# STLink_Schematic.net
KiCad netlist of a schematic drawn in Altium Designer
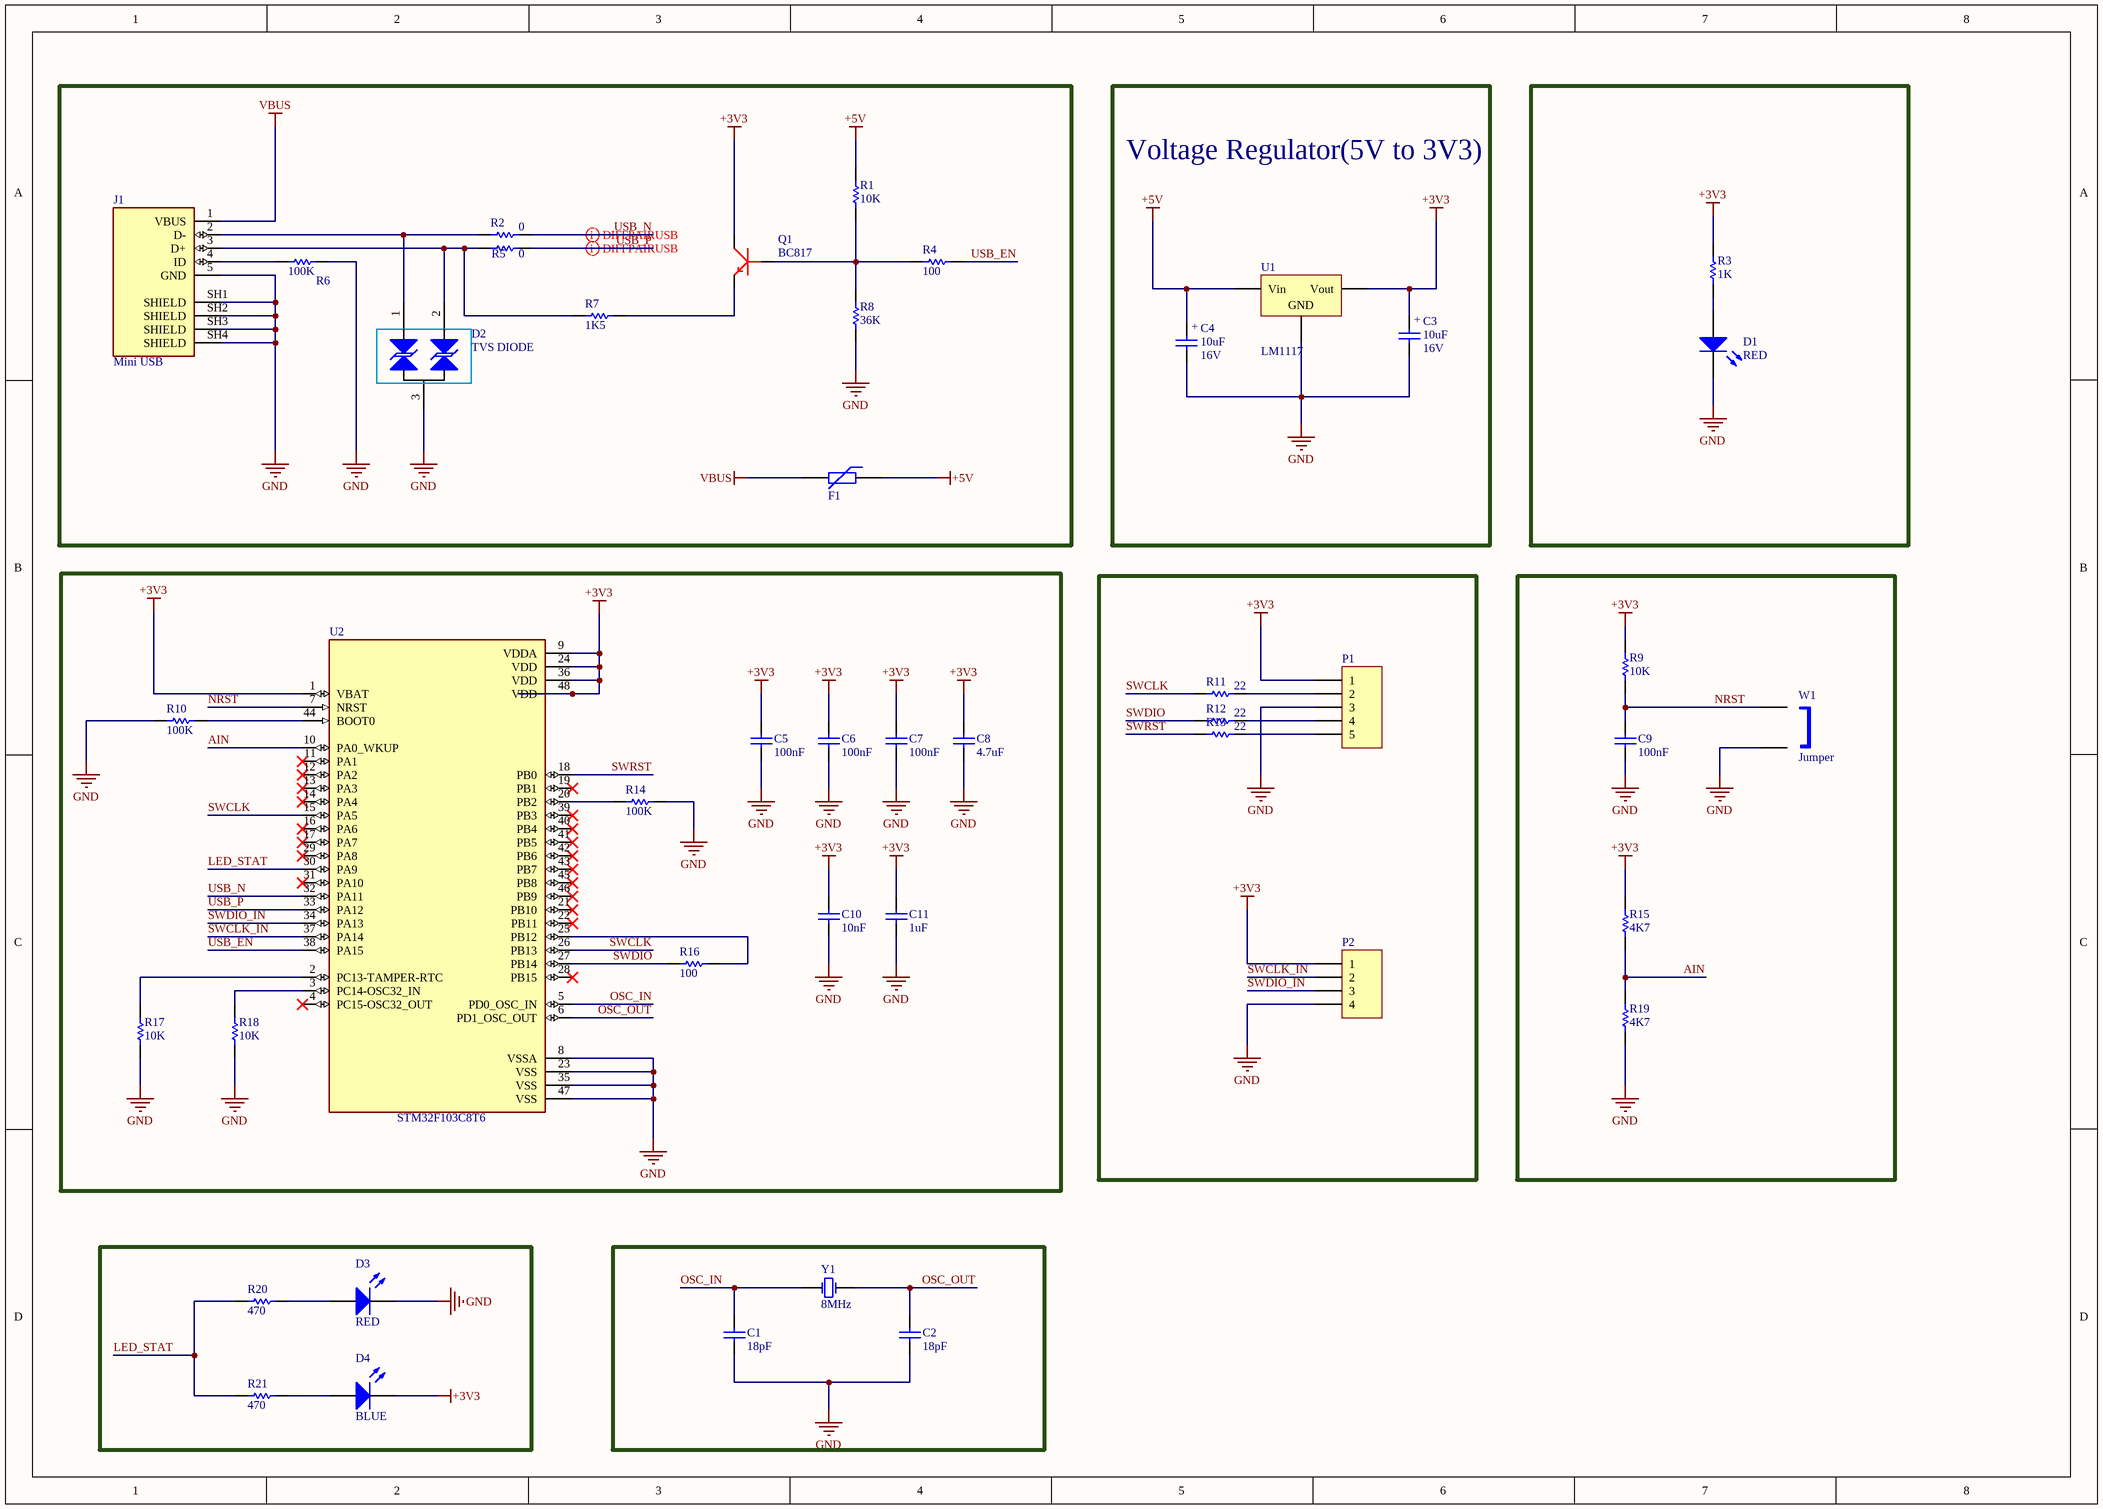
[diagram p0: STLink_Schematic.SchDoc]

(export (version "E")
  (design (tool "Eeschema 10.0.6"))
  (components
    (comp (ref "C1")
      (value "18pF")
      (footprint "C805")
      (description "Capacitor")
      (fields (field (name "DESIGNER") "Parsa Malekpour"))
      (libsource (lib "ParsaLibrary") (part "Cap"))
    )
    (comp (ref "C2")
      (value "18pF")
      (footprint "C805")
      (description "Capacitor")
      (fields (field (name "DESIGNER") "Parsa Malekpour"))
      (libsource (lib "ParsaLibrary") (part "Cap"))
    )
    (comp (ref "C3")
      (value "10uF")
      (footprint "MY_SMC_B")
      (description "Polar capacitor")
      (fields (field (name "ASID PART NUMBER") "C-AS") (field (name "VOLTE") "16V"))
      (libsource (lib "Mylib") (part "Cap Pol"))
    )
    (comp (ref "C4")
      (value "10uF")
      (footprint "MY_SMC_B")
      (description "Polar capacitor")
      (fields (field (name "ASID PART NUMBER") "C-AS") (field (name "VOLTE") "16V"))
      (libsource (lib "Mylib") (part "Cap Pol"))
    )
    (comp (ref "C5")
      (value "100nF")
      (footprint "C805")
      (description "Capacitor")
      (fields (field (name "DESIGNER") "Parsa Malekpour"))
      (libsource (lib "ParsaLibrary") (part "Cap"))
    )
    (comp (ref "C6")
      (value "100nF")
      (footprint "C805")
      (description "Capacitor")
      (fields (field (name "DESIGNER") "Parsa Malekpour"))
      (libsource (lib "ParsaLibrary") (part "Cap"))
    )
    (comp (ref "C7")
      (value "100nF")
      (footprint "C805")
      (description "Capacitor")
      (fields (field (name "DESIGNER") "Parsa Malekpour"))
      (libsource (lib "ParsaLibrary") (part "Cap"))
    )
    (comp (ref "C8")
      (value "4.7uF")
      (footprint "C805")
      (description "Capacitor")
      (fields (field (name "DESIGNER") "Parsa Malekpour"))
      (libsource (lib "ParsaLibrary") (part "Cap"))
    )
    (comp (ref "C9")
      (value "100nF")
      (footprint "C805")
      (description "Capacitor")
      (fields (field (name "DESIGNER") "Parsa Malekpour"))
      (libsource (lib "ParsaLibrary") (part "Cap"))
    )
    (comp (ref "C10")
      (value "10nF")
      (footprint "C805")
      (description "Capacitor")
      (fields (field (name "DESIGNER") "Parsa Malekpour"))
      (libsource (lib "ParsaLibrary") (part "Cap"))
    )
    (comp (ref "C11")
      (value "1uF")
      (footprint "C805")
      (description "Capacitor")
      (fields (field (name "DESIGNER") "Parsa Malekpour"))
      (libsource (lib "ParsaLibrary") (part "Cap"))
    )
    (comp (ref "D1")
      (value "RED")
      (footprint "MY_LED_1206")
      (description "Typical INFRARED GaAs LED")
      (fields (field (name "ASID PART NUMBER") "LED-AS"))
      (libsource (lib "Mylib") (part "LED"))
    )
    (comp (ref "D2") (value "TVS DIODE") (footprint "SOT-23") (libsource (lib "ParsaLibrary") (part "SM712")))
    (comp (ref "D3")
      (value "RED")
      (footprint "MY_LED_0805")
      (description "Typical INFRARED GaAs LED")
      (fields (field (name "ASID PART NUMBER") "LED-AS"))
      (libsource (lib "Mylib") (part "LED"))
    )
    (comp (ref "D4")
      (value "BLUE")
      (footprint "MY_LED_0805")
      (description "Typical INFRARED GaAs LED")
      (fields (field (name "ASID PART NUMBER") "LED-AS"))
      (libsource (lib "Mylib") (part "LED"))
    )
    (comp (ref "F1")
      (value "~")
      (footprint "PTC-0805")
      (description "PTC")
      (libsource (lib "ParsaLibrary") (part "PTC"))
    )
    (comp (ref "J1")
      (value "Mini USB")
      (footprint "MiniUSB")
      (description "MINI USB 2.0- B Type Receptacle conn. Right Angle Surface Mount Type")
      (fields (field (name "MF") "Amphenol ICC") (field (name "MP") "10033526-N3212LF"))
      (libsource (lib "STLink_V2_Design") (part "Mini USB"))
    )
    (comp (ref "P1")
      (value "Header 5")
      (footprint "My_1X05")
      (description "Header, 5-Pin")
      (fields (field (name "ASID PART NUMBER") "Header 5-AS"))
      (libsource (lib "Mylib") (part "Header 5"))
    )
    (comp (ref "P2")
      (value "Header 4")
      (footprint "My_1X04")
      (description "Header, 4-Pin")
      (fields (field (name "ASID PART NUMBER") "Header 4-AS"))
      (libsource (lib "Mylib") (part "Header 4"))
    )
    (comp (ref "Q1")
      (value "BC817")
      (footprint "SOT23_3")
      (libsource (lib "Led_Switching") (part "bc817-16"))
    )
    (comp (ref "R1")
      (value "10K")
      (footprint "R805")
      (description "Resistor")
      (fields (field (name "DESIGNER") "Parsa Malekpour"))
      (libsource (lib "ParsaLibrary") (part "Resistor"))
    )
    (comp (ref "R2")
      (value "0")
      (footprint "R805")
      (description "Resistor")
      (fields (field (name "DESIGNER") "Parsa Malekpour"))
      (libsource (lib "ParsaLibrary") (part "Resistor"))
    )
    (comp (ref "R3")
      (value "1K")
      (footprint "R805")
      (description "Resistor")
      (fields (field (name "DESIGNER") "Parsa Malekpour"))
      (libsource (lib "ParsaLibrary") (part "Resistor"))
    )
    (comp (ref "R4")
      (value "100")
      (footprint "R805")
      (description "Resistor")
      (fields (field (name "DESIGNER") "Parsa Malekpour"))
      (libsource (lib "ParsaLibrary") (part "Resistor"))
    )
    (comp (ref "R5")
      (value "0")
      (footprint "R805")
      (description "Resistor")
      (fields (field (name "DESIGNER") "Parsa Malekpour"))
      (libsource (lib "ParsaLibrary") (part "Resistor"))
    )
    (comp (ref "R6")
      (value "100K")
      (footprint "R805")
      (description "Resistor")
      (fields (field (name "DESIGNER") "Parsa Malekpour"))
      (libsource (lib "ParsaLibrary") (part "Resistor"))
    )
    (comp (ref "R7")
      (value "1K5")
      (footprint "R805")
      (description "Resistor")
      (fields (field (name "DESIGNER") "Parsa Malekpour"))
      (libsource (lib "ParsaLibrary") (part "Resistor"))
    )
    (comp (ref "R8")
      (value "36K")
      (footprint "R805")
      (description "Resistor")
      (fields (field (name "DESIGNER") "Parsa Malekpour"))
      (libsource (lib "ParsaLibrary") (part "Resistor"))
    )
    (comp (ref "R9")
      (value "10K")
      (footprint "R805")
      (description "Resistor")
      (fields (field (name "DESIGNER") "Parsa Malekpour"))
      (libsource (lib "ParsaLibrary") (part "Resistor"))
    )
    (comp (ref "R10")
      (value "100K")
      (footprint "R805")
      (description "Resistor")
      (fields (field (name "DESIGNER") "Parsa Malekpour"))
      (libsource (lib "ParsaLibrary") (part "Resistor"))
    )
    (comp (ref "R11")
      (value "22")
      (footprint "R805")
      (description "Resistor")
      (fields (field (name "DESIGNER") "Parsa Malekpour"))
      (libsource (lib "ParsaLibrary") (part "Resistor"))
    )
    (comp (ref "R12")
      (value "22")
      (footprint "R805")
      (description "Resistor")
      (fields (field (name "DESIGNER") "Parsa Malekpour"))
      (libsource (lib "ParsaLibrary") (part "Resistor"))
    )
    (comp (ref "R13")
      (value "22")
      (footprint "R805")
      (description "Resistor")
      (fields (field (name "DESIGNER") "Parsa Malekpour"))
      (libsource (lib "ParsaLibrary") (part "Resistor"))
    )
    (comp (ref "R14")
      (value "100K")
      (footprint "R805")
      (description "Resistor")
      (fields (field (name "DESIGNER") "Parsa Malekpour"))
      (libsource (lib "ParsaLibrary") (part "Resistor"))
    )
    (comp (ref "R15")
      (value "4K7")
      (footprint "R805")
      (description "Resistor")
      (fields (field (name "DESIGNER") "Parsa Malekpour"))
      (libsource (lib "ParsaLibrary") (part "Resistor"))
    )
    (comp (ref "R16")
      (value "100")
      (footprint "R805")
      (description "Resistor")
      (fields (field (name "DESIGNER") "Parsa Malekpour"))
      (libsource (lib "ParsaLibrary") (part "Resistor"))
    )
    (comp (ref "R17")
      (value "10K")
      (footprint "R805")
      (description "Resistor")
      (fields (field (name "DESIGNER") "Parsa Malekpour"))
      (libsource (lib "ParsaLibrary") (part "Resistor"))
    )
    (comp (ref "R18")
      (value "10K")
      (footprint "R805")
      (description "Resistor")
      (fields (field (name "DESIGNER") "Parsa Malekpour"))
      (libsource (lib "ParsaLibrary") (part "Resistor"))
    )
    (comp (ref "R19")
      (value "4K7")
      (footprint "R805")
      (description "Resistor")
      (fields (field (name "DESIGNER") "Parsa Malekpour"))
      (libsource (lib "ParsaLibrary") (part "Resistor"))
    )
    (comp (ref "R20")
      (value "470")
      (footprint "R805")
      (description "Resistor")
      (fields (field (name "DESIGNER") "Parsa Malekpour"))
      (libsource (lib "ParsaLibrary") (part "Resistor"))
    )
    (comp (ref "R21")
      (value "470")
      (footprint "R805")
      (description "Resistor")
      (fields (field (name "DESIGNER") "Parsa Malekpour"))
      (libsource (lib "ParsaLibrary") (part "Resistor"))
    )
    (comp (ref "U1")
      (value "LM1117")
      (footprint "MY_SOT223")
      (description "Low Drop Voltage Reg")
      (fields (field (name "ASID PART NUMBER") "LM1117-AS"))
      (libsource (lib "Mylib") (part "LM1117"))
    )
    (comp (ref "U2")
      (value "STM32F103C8T6")
      (footprint "QFP50P900X900X160-48N")
      (description "ARM® Cortex®-M3 STM32F1 Microcontroller IC 32-Bit 72MHz 64KB (64K x 8) FLASH 48-LQFP (7x7)")
      (fields (field (name "MF") "STMicroelectronics"))
      (libsource (lib "STLink_V2_Design") (part "STM32F103C8T6"))
    )
    (comp (ref "W1")
      (value "Jumper")
      (footprint "My_1X02")
      (description "Jumper Wire")
      (fields (field (name "ASID PART NUMBER") "Jumper-AS"))
      (libsource (lib "Mylib") (part "Jumper"))
    )
    (comp (ref "Y1")
      (value "8MHz")
      (footprint "XTAL-SMD")
      (description "Crystal Oscillator")
      (fields (field (name "DESIGNER") "Parsa Malekpour") (field (name "EMAIL") "Malekpour.parsa@Gmail.com"))
      (libsource (lib "ParsaLibrary") (part "XTAL"))
    )
  )
  (nets
    (net (code "1") (name "+3V3") (class "Default")
      (node (ref "C10") (pin "2") (pinfunction "2_2") (pintype "passive"))
      (node (ref "C11") (pin "2") (pinfunction "2_2") (pintype "passive"))
      (node (ref "C3") (pin "+") (pinfunction "+_+") (pintype "passive"))
      (node (ref "C5") (pin "2") (pinfunction "2_2") (pintype "passive"))
      (node (ref "C6") (pin "2") (pinfunction "2_2") (pintype "passive"))
      (node (ref "C7") (pin "2") (pinfunction "2_2") (pintype "passive"))
      (node (ref "C8") (pin "2") (pinfunction "2_2") (pintype "passive"))
      (node (ref "D4") (pin "K") (pinfunction "K_K") (pintype "passive"))
      (node (ref "P1") (pin "1") (pinfunction "1_1") (pintype "passive"))
      (node (ref "P2") (pin "1") (pinfunction "1_1") (pintype "passive"))
      (node (ref "Q1") (pin "3") (pinfunction "C_3") (pintype "passive"))
      (node (ref "R15") (pin "1") (pinfunction "1_1") (pintype "passive"))
      (node (ref "R3") (pin "2") (pinfunction "2_2") (pintype "passive"))
      (node (ref "R9") (pin "1") (pinfunction "1_1") (pintype "passive"))
      (node (ref "U1") (pin "2") (pinfunction "Vout_2") (pintype "passive"))
      (node (ref "U2") (pin "1") (pinfunction "VBAT_1") (pintype "bidirectional"))
      (node (ref "U2") (pin "24") (pinfunction "VDD_24") (pintype "power_in"))
      (node (ref "U2") (pin "36") (pinfunction "VDD_36") (pintype "power_in"))
      (node (ref "U2") (pin "48") (pinfunction "VDD_48") (pintype "power_in"))
      (node (ref "U2") (pin "9") (pinfunction "VDDA_9") (pintype "power_in"))
    )
    (net (code "2") (name "+5V") (class "Default")
      (node (ref "C4") (pin "+") (pinfunction "+_+") (pintype "passive"))
      (node (ref "F1") (pin "1") (pinfunction "1_1") (pintype "passive"))
      (node (ref "R1") (pin "2") (pinfunction "2_2") (pintype "passive"))
      (node (ref "U1") (pin "3") (pinfunction "Vin_3") (pintype "passive"))
    )
    (net (code "3") (name "/AIN") (class "Default")
      (node (ref "R15") (pin "2") (pinfunction "2_2") (pintype "passive"))
      (node (ref "R19") (pin "1") (pinfunction "1_1") (pintype "passive"))
      (node (ref "U2") (pin "10") (pinfunction "PA0_WKUP_10") (pintype "bidirectional"))
    )
    (net (code "4") (name "/LED_STAT") (class "Default")
      (node (ref "R20") (pin "2") (pinfunction "2_2") (pintype "passive"))
      (node (ref "R21") (pin "2") (pinfunction "2_2") (pintype "passive"))
      (node (ref "U2") (pin "30") (pinfunction "PA9_30") (pintype "bidirectional"))
    )
    (net (code "5") (name "/NRST") (class "Default")
      (node (ref "C9") (pin "2") (pinfunction "2_2") (pintype "passive"))
      (node (ref "R9") (pin "2") (pinfunction "2_2") (pintype "passive"))
      (node (ref "U2") (pin "7") (pinfunction "NRST_7") (pintype "input"))
      (node (ref "W1") (pin "1") (pinfunction "1_1") (pintype "passive"))
    )
    (net (code "6") (name "/OSC_IN") (class "Default")
      (node (ref "C1") (pin "2") (pinfunction "2_2") (pintype "passive"))
      (node (ref "U2") (pin "5") (pinfunction "PD0_OSC_IN_5") (pintype "bidirectional"))
      (node (ref "Y1") (pin "1") (pinfunction "OSC1_1") (pintype "passive"))
    )
    (net (code "7") (name "/OSC_OUT") (class "Default")
      (node (ref "C2") (pin "2") (pinfunction "2_2") (pintype "passive"))
      (node (ref "U2") (pin "6") (pinfunction "PD1_OSC_OUT_6") (pintype "bidirectional"))
      (node (ref "Y1") (pin "2") (pinfunction "OSC2_2") (pintype "passive"))
    )
    (net (code "8") (name "/SWCLK") (class "Default")
      (node (ref "R11") (pin "2") (pinfunction "2_2") (pintype "passive"))
      (node (ref "U2") (pin "15") (pinfunction "PA5_15") (pintype "bidirectional"))
      (node (ref "U2") (pin "26") (pinfunction "PB13_26") (pintype "bidirectional"))
    )
    (net (code "9") (name "/SWCLK_IN") (class "Default")
      (node (ref "P2") (pin "2") (pinfunction "2_2") (pintype "passive"))
      (node (ref "U2") (pin "37") (pinfunction "PA14_37") (pintype "bidirectional"))
    )
    (net (code "10") (name "/SWDIO") (class "Default")
      (node (ref "R12") (pin "2") (pinfunction "2_2") (pintype "passive"))
      (node (ref "R16") (pin "2") (pinfunction "2_2") (pintype "passive"))
      (node (ref "U2") (pin "27") (pinfunction "PB14_27") (pintype "bidirectional"))
    )
    (net (code "11") (name "/SWDIO_IN") (class "Default")
      (node (ref "P2") (pin "3") (pinfunction "3_3") (pintype "passive"))
      (node (ref "U2") (pin "34") (pinfunction "PA13_34") (pintype "bidirectional"))
    )
    (net (code "12") (name "/SWRST") (class "Default")
      (node (ref "R13") (pin "2") (pinfunction "2_2") (pintype "passive"))
      (node (ref "U2") (pin "18") (pinfunction "PB0_18") (pintype "bidirectional"))
    )
    (net (code "13") (name "/USB_EN") (class "Default")
      (node (ref "R4") (pin "1") (pinfunction "1_1") (pintype "passive"))
      (node (ref "U2") (pin "38") (pinfunction "PA15_38") (pintype "bidirectional"))
    )
    (net (code "14") (name "/USB_N") (class "Default")
      (node (ref "R2") (pin "2") (pinfunction "2_2") (pintype "passive"))
      (node (ref "U2") (pin "32") (pinfunction "PA11_32") (pintype "bidirectional"))
    )
    (net (code "15") (name "/USB_P") (class "Default")
      (node (ref "R5") (pin "2") (pinfunction "2_2") (pintype "passive"))
      (node (ref "U2") (pin "33") (pinfunction "PA12_33") (pintype "bidirectional"))
    )
    (net (code "16") (name "GND") (class "Default")
      (node (ref "C1") (pin "1") (pinfunction "1_1") (pintype "passive"))
      (node (ref "C10") (pin "1") (pinfunction "1_1") (pintype "passive"))
      (node (ref "C11") (pin "1") (pinfunction "1_1") (pintype "passive"))
      (node (ref "C2") (pin "1") (pinfunction "1_1") (pintype "passive"))
      (node (ref "C3") (pin "-") (pinfunction "-_-") (pintype "passive"))
      (node (ref "C4") (pin "-") (pinfunction "-_-") (pintype "passive"))
      (node (ref "C5") (pin "1") (pinfunction "1_1") (pintype "passive"))
      (node (ref "C6") (pin "1") (pinfunction "1_1") (pintype "passive"))
      (node (ref "C7") (pin "1") (pinfunction "1_1") (pintype "passive"))
      (node (ref "C8") (pin "1") (pinfunction "1_1") (pintype "passive"))
      (node (ref "C9") (pin "1") (pinfunction "1_1") (pintype "passive"))
      (node (ref "D1") (pin "K") (pinfunction "K_K") (pintype "passive"))
      (node (ref "D2") (pin "3") (pinfunction "A_3") (pintype "passive"))
      (node (ref "D3") (pin "K") (pinfunction "K_K") (pintype "passive"))
      (node (ref "J1") (pin "5") (pinfunction "GND_5") (pintype "power_in"))
      (node (ref "J1") (pin "SH1") (pinfunction "SHIELD_SH1") (pintype "passive"))
      (node (ref "J1") (pin "SH2") (pinfunction "SHIELD_SH2") (pintype "passive"))
      (node (ref "J1") (pin "SH3") (pinfunction "SHIELD_SH3") (pintype "passive"))
      (node (ref "J1") (pin "SH4") (pinfunction "SHIELD_SH4") (pintype "passive"))
      (node (ref "P1") (pin "3") (pinfunction "3_3") (pintype "passive"))
      (node (ref "P2") (pin "4") (pinfunction "4_4") (pintype "passive"))
      (node (ref "R10") (pin "2") (pinfunction "2_2") (pintype "passive"))
      (node (ref "R14") (pin "1") (pinfunction "1_1") (pintype "passive"))
      (node (ref "R17") (pin "2") (pinfunction "2_2") (pintype "passive"))
      (node (ref "R18") (pin "2") (pinfunction "2_2") (pintype "passive"))
      (node (ref "R19") (pin "2") (pinfunction "2_2") (pintype "passive"))
      (node (ref "R6") (pin "2") (pinfunction "2_2") (pintype "passive"))
      (node (ref "R8") (pin "1") (pinfunction "1_1") (pintype "passive"))
      (node (ref "U1") (pin "1") (pinfunction "GND_1") (pintype "passive"))
      (node (ref "U2") (pin "23") (pinfunction "VSS_23") (pintype "power_in"))
      (node (ref "U2") (pin "35") (pinfunction "VSS_35") (pintype "power_in"))
      (node (ref "U2") (pin "47") (pinfunction "VSS_47") (pintype "power_in"))
      (node (ref "U2") (pin "8") (pinfunction "VSSA_8") (pintype "power_in"))
      (node (ref "W1") (pin "2") (pinfunction "2_2") (pintype "passive"))
    )
    (net (code "17") (name "Net-(D1-PadA)") (class "Default")
      (node (ref "D1") (pin "A") (pinfunction "A_A") (pintype "passive"))
      (node (ref "R3") (pin "1") (pinfunction "1_1") (pintype "passive"))
    )
    (net (code "18") (name "Net-(D3-PadA)") (class "Default")
      (node (ref "D3") (pin "A") (pinfunction "A_A") (pintype "passive"))
      (node (ref "R20") (pin "1") (pinfunction "1_1") (pintype "passive"))
    )
    (net (code "19") (name "Net-(D4-PadA)") (class "Default")
      (node (ref "D4") (pin "A") (pinfunction "A_A") (pintype "passive"))
      (node (ref "R21") (pin "1") (pinfunction "1_1") (pintype "passive"))
    )
    (net (code "20") (name "Net-(J1-D+)") (class "Default")
      (node (ref "D2") (pin "2") (pinfunction "K_2") (pintype "passive"))
      (node (ref "J1") (pin "3") (pinfunction "D+_3") (pintype "bidirectional"))
      (node (ref "R5") (pin "1") (pinfunction "1_1") (pintype "passive"))
      (node (ref "R7") (pin "1") (pinfunction "1_1") (pintype "passive"))
    )
    (net (code "21") (name "Net-(J1-D-)") (class "Default")
      (node (ref "D2") (pin "1") (pinfunction "K_1") (pintype "passive"))
      (node (ref "J1") (pin "2") (pinfunction "D-_2") (pintype "bidirectional"))
      (node (ref "R2") (pin "1") (pinfunction "1_1") (pintype "passive"))
    )
    (net (code "22") (name "Net-(J1-ID)") (class "Default")
      (node (ref "J1") (pin "4") (pinfunction "ID_4") (pintype "bidirectional"))
      (node (ref "R6") (pin "1") (pinfunction "1_1") (pintype "passive"))
    )
    (net (code "23") (name "Net-(P1-Pad2)") (class "Default")
      (node (ref "P1") (pin "2") (pinfunction "2_2") (pintype "passive"))
      (node (ref "R11") (pin "1") (pinfunction "1_1") (pintype "passive"))
    )
    (net (code "24") (name "Net-(P1-Pad4)") (class "Default")
      (node (ref "P1") (pin "4") (pinfunction "4_4") (pintype "passive"))
      (node (ref "R12") (pin "1") (pinfunction "1_1") (pintype "passive"))
    )
    (net (code "25") (name "Net-(P1-Pad5)") (class "Default")
      (node (ref "P1") (pin "5") (pinfunction "5_5") (pintype "passive"))
      (node (ref "R13") (pin "1") (pinfunction "1_1") (pintype "passive"))
    )
    (net (code "26") (name "Net-(Q1-B)") (class "Default")
      (node (ref "Q1") (pin "1") (pinfunction "B_1") (pintype "passive"))
      (node (ref "R1") (pin "1") (pinfunction "1_1") (pintype "passive"))
      (node (ref "R4") (pin "2") (pinfunction "2_2") (pintype "passive"))
      (node (ref "R8") (pin "2") (pinfunction "2_2") (pintype "passive"))
    )
    (net (code "27") (name "Net-(Q1-E)") (class "Default")
      (node (ref "Q1") (pin "2") (pinfunction "E_2") (pintype "passive"))
      (node (ref "R7") (pin "2") (pinfunction "2_2") (pintype "passive"))
    )
    (net (code "28") (name "Net-(U2-BOOT0)") (class "Default")
      (node (ref "R10") (pin "1") (pinfunction "1_1") (pintype "passive"))
      (node (ref "U2") (pin "44") (pinfunction "BOOT0_44") (pintype "input"))
    )
    (net (code "29") (name "Net-(U2-PB2)") (class "Default")
      (node (ref "R14") (pin "2") (pinfunction "2_2") (pintype "passive"))
      (node (ref "U2") (pin "20") (pinfunction "PB2_20") (pintype "bidirectional"))
    )
    (net (code "30") (name "Net-(U2-PB12)") (class "Default")
      (node (ref "R16") (pin "1") (pinfunction "1_1") (pintype "passive"))
      (node (ref "U2") (pin "25") (pinfunction "PB12_25") (pintype "bidirectional"))
    )
    (net (code "31") (name "Net-(U2-PC13-TAMPER-RTC)") (class "Default")
      (node (ref "R17") (pin "1") (pinfunction "1_1") (pintype "passive"))
      (node (ref "U2") (pin "2") (pinfunction "PC13-TAMPER-RTC_2") (pintype "bidirectional"))
    )
    (net (code "32") (name "Net-(U2-PC14-OSC32_IN)") (class "Default")
      (node (ref "R18") (pin "1") (pinfunction "1_1") (pintype "passive"))
      (node (ref "U2") (pin "3") (pinfunction "PC14-OSC32_IN_3") (pintype "bidirectional"))
    )
    (net (code "33") (name "VBUS") (class "Default")
      (node (ref "F1") (pin "2") (pinfunction "2_2") (pintype "passive"))
      (node (ref "J1") (pin "1") (pinfunction "VBUS_1") (pintype "power_in"))
    )
    (net (code "34") (name "unconnected-(U2-PA1-Pad11)") (class "Default")
      (node (ref "U2") (pin "11") (pinfunction "PA1_11") (pintype "bidirectional+no_connect"))
    )
    (net (code "35") (name "unconnected-(U2-PA2-Pad12)") (class "Default")
      (node (ref "U2") (pin "12") (pinfunction "PA2_12") (pintype "bidirectional+no_connect"))
    )
    (net (code "36") (name "unconnected-(U2-PA3-Pad13)") (class "Default")
      (node (ref "U2") (pin "13") (pinfunction "PA3_13") (pintype "bidirectional+no_connect"))
    )
    (net (code "37") (name "unconnected-(U2-PA4-Pad14)") (class "Default")
      (node (ref "U2") (pin "14") (pinfunction "PA4_14") (pintype "bidirectional+no_connect"))
    )
    (net (code "38") (name "unconnected-(U2-PA6-Pad16)") (class "Default")
      (node (ref "U2") (pin "16") (pinfunction "PA6_16") (pintype "bidirectional+no_connect"))
    )
    (net (code "39") (name "unconnected-(U2-PA7-Pad17)") (class "Default")
      (node (ref "U2") (pin "17") (pinfunction "PA7_17") (pintype "bidirectional+no_connect"))
    )
    (net (code "40") (name "unconnected-(U2-PA8-Pad29)") (class "Default")
      (node (ref "U2") (pin "29") (pinfunction "PA8_29") (pintype "bidirectional+no_connect"))
    )
    (net (code "41") (name "unconnected-(U2-PA10-Pad31)") (class "Default")
      (node (ref "U2") (pin "31") (pinfunction "PA10_31") (pintype "bidirectional+no_connect"))
    )
    (net (code "42") (name "unconnected-(U2-PB1-Pad19)") (class "Default")
      (node (ref "U2") (pin "19") (pinfunction "PB1_19") (pintype "bidirectional+no_connect"))
    )
    (net (code "43") (name "unconnected-(U2-PB3-Pad39)") (class "Default")
      (node (ref "U2") (pin "39") (pinfunction "PB3_39") (pintype "bidirectional+no_connect"))
    )
    (net (code "44") (name "unconnected-(U2-PB4-Pad40)") (class "Default")
      (node (ref "U2") (pin "40") (pinfunction "PB4_40") (pintype "bidirectional+no_connect"))
    )
    (net (code "45") (name "unconnected-(U2-PB5-Pad41)") (class "Default")
      (node (ref "U2") (pin "41") (pinfunction "PB5_41") (pintype "bidirectional+no_connect"))
    )
    (net (code "46") (name "unconnected-(U2-PB6-Pad42)") (class "Default")
      (node (ref "U2") (pin "42") (pinfunction "PB6_42") (pintype "bidirectional+no_connect"))
    )
    (net (code "47") (name "unconnected-(U2-PB7-Pad43)") (class "Default")
      (node (ref "U2") (pin "43") (pinfunction "PB7_43") (pintype "bidirectional+no_connect"))
    )
    (net (code "48") (name "unconnected-(U2-PB8-Pad45)") (class "Default")
      (node (ref "U2") (pin "45") (pinfunction "PB8_45") (pintype "bidirectional+no_connect"))
    )
    (net (code "49") (name "unconnected-(U2-PB9-Pad46)") (class "Default")
      (node (ref "U2") (pin "46") (pinfunction "PB9_46") (pintype "bidirectional+no_connect"))
    )
    (net (code "50") (name "unconnected-(U2-PB10-Pad21)") (class "Default")
      (node (ref "U2") (pin "21") (pinfunction "PB10_21") (pintype "bidirectional+no_connect"))
    )
    (net (code "51") (name "unconnected-(U2-PB11-Pad22)") (class "Default")
      (node (ref "U2") (pin "22") (pinfunction "PB11_22") (pintype "bidirectional+no_connect"))
    )
    (net (code "52") (name "unconnected-(U2-PB15-Pad28)") (class "Default")
      (node (ref "U2") (pin "28") (pinfunction "PB15_28") (pintype "bidirectional+no_connect"))
    )
    (net (code "53") (name "unconnected-(U2-PC15-OSC32_OUT-Pad4)") (class "Default")
      (node (ref "U2") (pin "4") (pinfunction "PC15-OSC32_OUT_4") (pintype "bidirectional+no_connect"))
    )
  )
)
